# power.net
KiCad netlist of a schematic drawn in Altium Designer
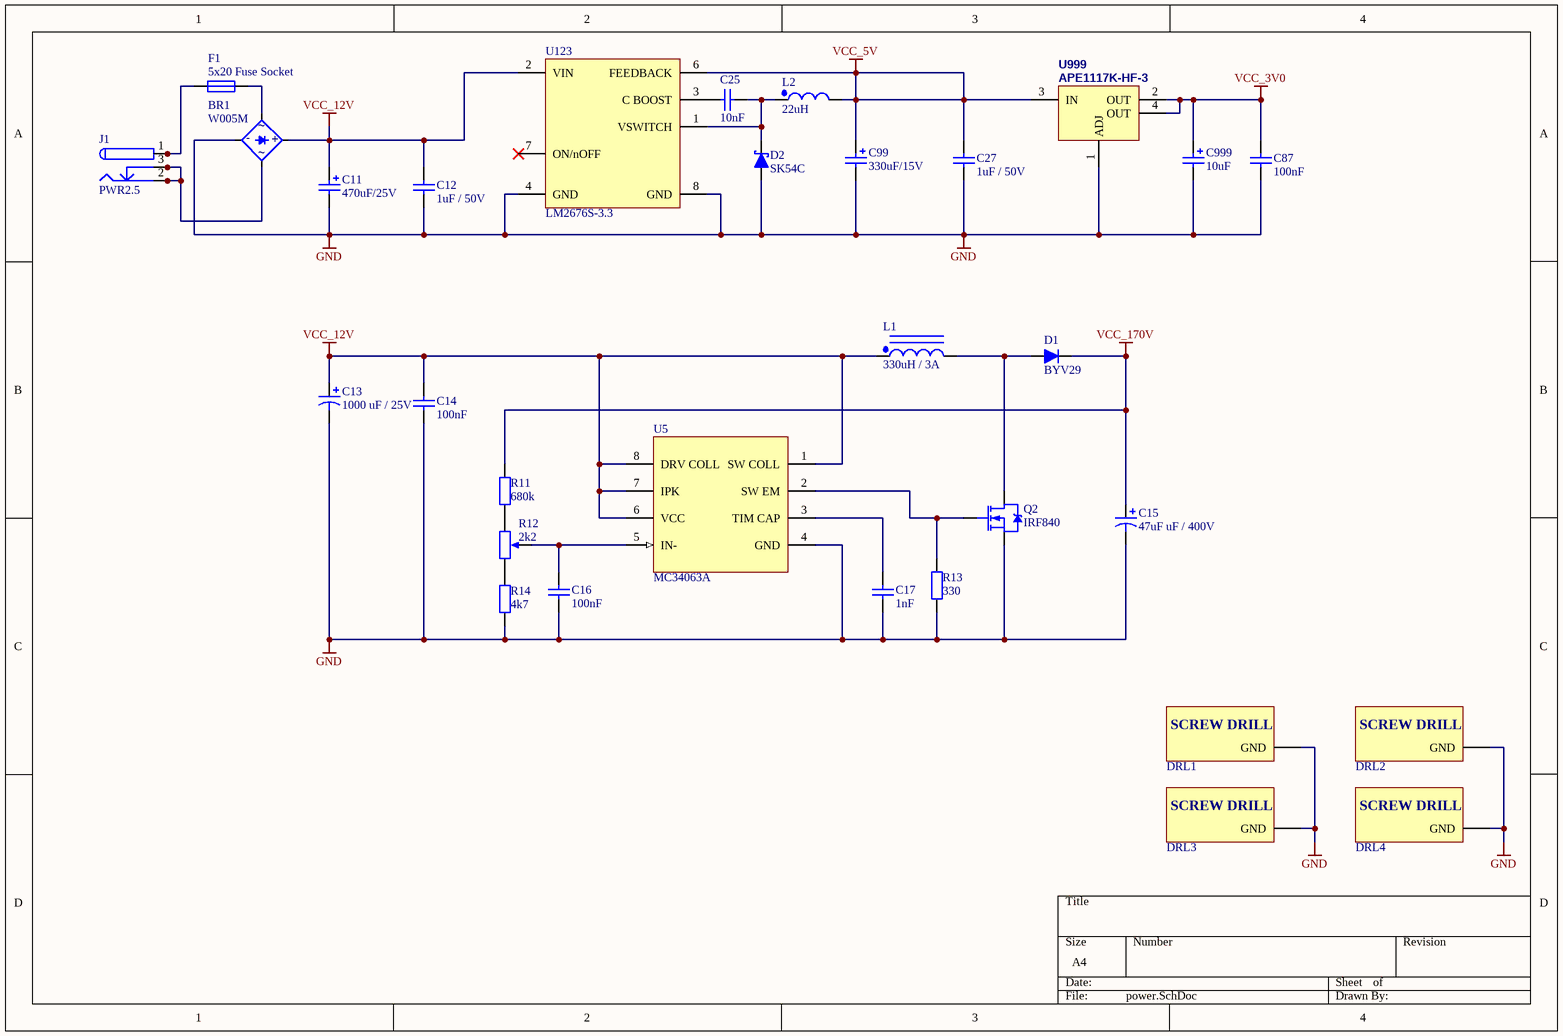
[diagram p0: power.SchDoc]

(export (version "E")
  (design (tool "Eeschema 10.0.6"))
  (components
    (comp (ref "BR1")
      (value "W005M")
      (footprint "WxxM")
      (description "50V, 1,5A, Single Phase Silicone Bridge Rectifier, DC Components")
      (fields (field (name "PUBLISHER") "Altium Limited"))
      (libsource (lib "bridge_rectifiers") (part "W005M"))
    )
    (comp (ref "C11")
      (value "470uF/25V")
      (footprint "SMDC")
      (description "Polarized Tantalum Capacitor")
      (libsource (lib "capacitors") (part "Cap Pol Tant"))
    )
    (comp (ref "C12")
      (value "1uF / 50V")
      (footprint "C0805")
      (description "Capacitor")
      (libsource (lib "capacitors") (part "Cap"))
    )
    (comp (ref "C13")
      (value "1000 uF / 25V")
      (footprint "CE10x20-5_RA")
      (description "Polarized Capacitor")
      (libsource (lib "capacitors") (part "Cap Pol"))
    )
    (comp (ref "C14")
      (value "100nF")
      (footprint "C0805")
      (description "Capacitor")
      (libsource (lib "capacitors") (part "Cap"))
    )
    (comp (ref "C15")
      (value "47uF uF / 400V")
      (footprint "CE10x20-5_RA")
      (description "Polarized Capacitor")
      (libsource (lib "capacitors") (part "Cap Pol"))
    )
    (comp (ref "C16")
      (value "100nF")
      (footprint "C0805")
      (description "Capacitor")
      (libsource (lib "capacitors") (part "Cap"))
    )
    (comp (ref "C17")
      (value "1nF")
      (footprint "C0805")
      (description "Capacitor")
      (libsource (lib "capacitors") (part "Cap"))
    )
    (comp (ref "C25")
      (value "10nF")
      (footprint "C0805")
      (description "Capacitor")
      (libsource (lib "capacitors") (part "Cap"))
    )
    (comp (ref "C27")
      (value "1uF / 50V")
      (footprint "C0805")
      (description "Capacitor")
      (libsource (lib "capacitors") (part "Cap"))
    )
    (comp (ref "C87")
      (value "100nF")
      (footprint "C0805")
      (description "Capacitor")
      (libsource (lib "capacitors") (part "Cap"))
    )
    (comp (ref "C99")
      (value "330uF/15V")
      (footprint "SMDC")
      (description "Polarized Tantalum Capacitor")
      (libsource (lib "capacitors") (part "Cap Pol Tant"))
    )
    (comp (ref "C999")
      (value "10uF")
      (footprint "SMDB")
      (description "Polarized Tantalum Capacitor")
      (libsource (lib "capacitors") (part "Cap Pol Tant"))
    )
    (comp (ref "D1")
      (value "BYV29")
      (footprint "TO-220-2_RA")
      (description "Rectifier diodes ultrafast")
      (libsource (lib "diodes_other") (part "BYV29"))
    )
    (comp (ref "D2")
      (value "SK54C")
      (footprint "SMC")
      (description "Schottky Diode: 40V, 5A")
      (libsource (lib "diodes_schottky") (part "SK54C"))
    )
    (comp (ref "DRL1")
      (value "SCREW DRILL")
      (footprint "3mm screw drill I")
      (description "Screw Drill")
      (libsource (lib "main_lib") (part "SCREW DRILL"))
    )
    (comp (ref "DRL2")
      (value "SCREW DRILL")
      (footprint "3mm screw drill I")
      (description "Screw Drill")
      (libsource (lib "main_lib") (part "SCREW DRILL"))
    )
    (comp (ref "DRL3")
      (value "SCREW DRILL")
      (footprint "3mm screw drill I")
      (description "Screw Drill")
      (libsource (lib "main_lib") (part "SCREW DRILL"))
    )
    (comp (ref "DRL4")
      (value "SCREW DRILL")
      (footprint "3mm screw drill I")
      (description "Screw Drill")
      (libsource (lib "main_lib") (part "SCREW DRILL"))
    )
    (comp (ref "F1")
      (value "5x20 Fuse Socket")
      (footprint "Bezp 5x20 uniw II")
      (fields (field (name "PUBLISHER") "Altium Limited"))
      (libsource (lib "fuses") (part "Fuse Socket"))
    )
    (comp (ref "J1")
      (value "PWR2.5")
      (footprint "KLD-0202")
      (description "Low Voltage Power Supply Connector")
      (fields (field (name "PUBLISHER") "Altium Limited"))
      (libsource (lib "connectors_other") (part "PWR2.5"))
    )
    (comp (ref "L1")
      (value "330uH / 3A")
      (footprint "IND_15_POZIOMO")
      (description "Magnetic-Core Inductor with Winding Polarity Marking")
      (libsource (lib "main_lib_sch") (part "InducCore"))
    )
    (comp (ref "L2")
      (value "22uH")
      (footprint "DE1207")
      (description "Inductor")
      (libsource (lib "inductors") (part "Ind"))
    )
    (comp (ref "Q2")
      (value "IRF840")
      (footprint "TO-220AB_RA_H1")
      (description "N-Channel Power MOSFET")
      (libsource (lib "transistors_other") (part "IRF840"))
    )
    (comp (ref "R11")
      (value "680k")
      (footprint "R0805")
      (description "Resistor")
      (libsource (lib "resistors") (part "Res"))
    )
    (comp (ref "R12")
      (value "2k2")
      (footprint "RPot_wieloob_19mm_lezacy")
      (description "Potentiometer")
      (libsource (lib "main_lib_sch") (part "RPot"))
    )
    (comp (ref "R13")
      (value "330")
      (footprint "R0805")
      (description "Resistor")
      (libsource (lib "resistors") (part "Res"))
    )
    (comp (ref "R14")
      (value "4k7")
      (footprint "R0805")
      (description "Resistor")
      (libsource (lib "resistors") (part "Res"))
    )
    (comp (ref "U5")
      (value "MC34063A")
      (footprint "SO8")
      (description "1.5 A, Step-Up/Down/Inverting Switching Regulator")
      (libsource (lib "switched_voltage_regulators") (part "MC34063A"))
    )
    (comp (ref "U123")
      (value "LM2676S-3.3")
      (footprint "TO-263-7 (D2PAK-7)")
      (description "High Efficiency 3A Step-Down Simple Switcher 3.3V Regulator in TO-263 (D2PAK)")
      (libsource (lib "switched_voltage_regulators") (part "LM2676S-3.3"))
    )
    (comp (ref "U999")
      (value "APE1117K-HF-3")
      (footprint "SOT-223")
      (description "800mA Low-Dropout Adjustable, 1A Linear Regulator, SOT223 Package")
      (fields (field (name "PUBLISHER") "Altium Limited"))
      (libsource (lib "linear_voltage_regulators") (part "APE1117K-HF-3"))
    )
  )
  (nets
    (net (code "1") (name "GND") (class "Default")
      (node (ref "BR1") (pin "4") (pinfunction "-_4") (pintype "power_in"))
      (node (ref "C11") (pin "2") (pinfunction "2_2") (pintype "passive"))
      (node (ref "C12") (pin "1") (pinfunction "1_1") (pintype "passive"))
      (node (ref "C13") (pin "2") (pinfunction "2_2") (pintype "passive"))
      (node (ref "C14") (pin "1") (pinfunction "1_1") (pintype "passive"))
      (node (ref "C15") (pin "2") (pinfunction "2_2") (pintype "passive"))
      (node (ref "C16") (pin "1") (pinfunction "1_1") (pintype "passive"))
      (node (ref "C17") (pin "1") (pinfunction "1_1") (pintype "passive"))
      (node (ref "C27") (pin "1") (pinfunction "1_1") (pintype "passive"))
      (node (ref "C87") (pin "1") (pinfunction "1_1") (pintype "passive"))
      (node (ref "C99") (pin "2") (pinfunction "2_2") (pintype "passive"))
      (node (ref "C999") (pin "2") (pinfunction "2_2") (pintype "passive"))
      (node (ref "D2") (pin "1") (pinfunction "A_1") (pintype "passive"))
      (node (ref "DRL1") (pin "0") (pinfunction "GND_0") (pintype "passive"))
      (node (ref "DRL2") (pin "0") (pinfunction "GND_0") (pintype "passive"))
      (node (ref "DRL3") (pin "0") (pinfunction "GND_0") (pintype "passive"))
      (node (ref "DRL4") (pin "0") (pinfunction "GND_0") (pintype "passive"))
      (node (ref "Q2") (pin "3") (pinfunction "S_3") (pintype "passive"))
      (node (ref "R13") (pin "1") (pinfunction "1_1") (pintype "passive"))
      (node (ref "R14") (pin "1") (pinfunction "1_1") (pintype "passive"))
      (node (ref "U123") (pin "4") (pinfunction "GND_4") (pintype "power_in"))
      (node (ref "U123") (pin "8") (pinfunction "GND_8") (pintype "power_in"))
      (node (ref "U5") (pin "4") (pinfunction "GND_4") (pintype "power_in"))
      (node (ref "U999") (pin "1") (pinfunction "ADJ_1") (pintype "power_in"))
    )
    (net (code "2") (name "Net-(BR1-AC-Pad2)") (class "Default")
      (node (ref "BR1") (pin "2") (pinfunction "AC_2") (pintype "power_in"))
      (node (ref "F1") (pin "2") (pinfunction "2_2") (pintype "passive"))
    )
    (net (code "3") (name "Net-(BR1-AC-Pad3)") (class "Default")
      (node (ref "BR1") (pin "3") (pinfunction "AC_3") (pintype "power_in"))
      (node (ref "J1") (pin "2") (pinfunction "2_2") (pintype "power_in"))
      (node (ref "J1") (pin "2A") (pinfunction "2A_2A") (pintype "power_in"))
      (node (ref "J1") (pin "2B") (pinfunction "2B_2B") (pintype "power_in"))
      (node (ref "J1") (pin "3") (pinfunction "3_3") (pintype "power_in"))
      (node (ref "J1") (pin "3A") (pinfunction "3A_3A") (pintype "power_in"))
      (node (ref "J1") (pin "3B") (pinfunction "3B_3B") (pintype "power_in"))
    )
    (net (code "4") (name "Net-(D1-A)") (class "Default")
      (node (ref "D1") (pin "1") (pinfunction "A_1") (pintype "passive"))
      (node (ref "L1") (pin "2") (pinfunction "2_2") (pintype "passive"))
      (node (ref "Q2") (pin "2") (pinfunction "D_2") (pintype "passive"))
    )
    (net (code "5") (name "Net-(D2-K)") (class "Default")
      (node (ref "C25") (pin "1") (pinfunction "1_1") (pintype "passive"))
      (node (ref "D2") (pin "2") (pinfunction "K_2") (pintype "passive"))
      (node (ref "L2") (pin "1") (pinfunction "1_1") (pintype "passive"))
      (node (ref "U123") (pin "1") (pinfunction "VSWITCH_1") (pintype "passive"))
    )
    (net (code "6") (name "Net-(F1-Pad1)") (class "Default")
      (node (ref "F1") (pin "1") (pinfunction "1_1") (pintype "passive"))
      (node (ref "J1") (pin "1") (pinfunction "1_1") (pintype "power_in"))
      (node (ref "J1") (pin "1A") (pinfunction "1A_1A") (pintype "power_in"))
      (node (ref "J1") (pin "1B") (pinfunction "1B_1B") (pintype "power_in"))
    )
    (net (code "7") (name "Net-(Q2-G)") (class "Default")
      (node (ref "Q2") (pin "1") (pinfunction "G_1") (pintype "passive"))
      (node (ref "R13") (pin "2") (pinfunction "2_2") (pintype "passive"))
      (node (ref "U5") (pin "2") (pinfunction "SW_EM_2") (pintype "passive"))
    )
    (net (code "8") (name "Net-(R12-BOT)") (class "Default")
      (node (ref "R11") (pin "1") (pinfunction "1_1") (pintype "passive"))
      (node (ref "R12") (pin "2") (pinfunction "BOT_2") (pintype "passive"))
    )
    (net (code "9") (name "Net-(R12-TAP)") (class "Default")
      (node (ref "C16") (pin "2") (pinfunction "2_2") (pintype "passive"))
      (node (ref "R12") (pin "3") (pinfunction "TAP_3") (pintype "passive"))
      (node (ref "U5") (pin "5") (pinfunction "IN-_5") (pintype "input"))
    )
    (net (code "10") (name "Net-(R12-TOP)") (class "Default")
      (node (ref "R12") (pin "1") (pinfunction "TOP_1") (pintype "passive"))
      (node (ref "R14") (pin "2") (pinfunction "2_2") (pintype "passive"))
    )
    (net (code "11") (name "Net-(U5-TIM_CAP)") (class "Default")
      (node (ref "C17") (pin "2") (pinfunction "2_2") (pintype "passive"))
      (node (ref "U5") (pin "3") (pinfunction "TIM_CAP_3") (pintype "passive"))
    )
    (net (code "12") (name "Net-(U123-C_BOOST)") (class "Default")
      (node (ref "C25") (pin "2") (pinfunction "2_2") (pintype "passive"))
      (node (ref "U123") (pin "3") (pinfunction "C_BOOST_3") (pintype "passive"))
    )
    (net (code "13") (name "VCC_3V0") (class "Default")
      (node (ref "C87") (pin "2") (pinfunction "2_2") (pintype "passive"))
      (node (ref "C999") (pin "1") (pinfunction "1_1") (pintype "passive"))
      (node (ref "U999") (pin "2") (pinfunction "OUT_2") (pintype "power_in"))
      (node (ref "U999") (pin "4") (pinfunction "OUT_4") (pintype "power_in"))
    )
    (net (code "14") (name "VCC_5V") (class "Default")
      (node (ref "C27") (pin "2") (pinfunction "2_2") (pintype "passive"))
      (node (ref "C99") (pin "1") (pinfunction "1_1") (pintype "passive"))
      (node (ref "L2") (pin "2") (pinfunction "2_2") (pintype "passive"))
      (node (ref "U123") (pin "6") (pinfunction "FEEDBACK_6") (pintype "power_in"))
      (node (ref "U999") (pin "3") (pinfunction "IN_3") (pintype "power_in"))
    )
    (net (code "15") (name "VCC_12V") (class "Default")
      (node (ref "BR1") (pin "1") (pinfunction "+_1") (pintype "power_in"))
      (node (ref "C11") (pin "1") (pinfunction "1_1") (pintype "passive"))
      (node (ref "C12") (pin "2") (pinfunction "2_2") (pintype "passive"))
      (node (ref "C13") (pin "1") (pinfunction "1_1") (pintype "passive"))
      (node (ref "C14") (pin "2") (pinfunction "2_2") (pintype "passive"))
      (node (ref "L1") (pin "1") (pinfunction "1_1") (pintype "passive"))
      (node (ref "U123") (pin "2") (pinfunction "VIN_2") (pintype "power_in"))
      (node (ref "U5") (pin "1") (pinfunction "SW_COLL_1") (pintype "passive"))
      (node (ref "U5") (pin "6") (pinfunction "VCC_6") (pintype "power_in"))
      (node (ref "U5") (pin "7") (pinfunction "IPK_7") (pintype "passive"))
      (node (ref "U5") (pin "8") (pinfunction "DRV_COLL_8") (pintype "open_collector"))
    )
    (net (code "16") (name "VCC_170V") (class "Default")
      (node (ref "C15") (pin "1") (pinfunction "1_1") (pintype "passive"))
      (node (ref "D1") (pin "2") (pinfunction "K_2") (pintype "passive"))
      (node (ref "R11") (pin "2") (pinfunction "2_2") (pintype "passive"))
    )
    (net (code "17") (name "unconnected-(U123-NC-Pad5)") (class "Default")
      (node (ref "U123") (pin "5") (pinfunction "NC_5") (pintype "passive"))
    )
    (net (code "18") (name "unconnected-(U123-ON{slash}nOFF-Pad7)") (class "Default")
      (node (ref "U123") (pin "7") (pinfunction "ON/nOFF_7") (pintype "passive+no_connect"))
    )
  )
)
